# SubBus1.net
KiCad netlist of a schematic drawn in Altium Designer
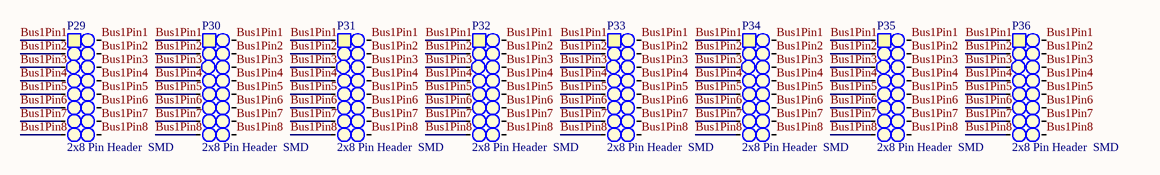
[diagram p0: SubBus1.SchDoc]

(export (version "E")
  (design (tool "Eeschema 10.0.6"))
  (components
    (comp (ref "P29")
      (value "2x8 Pin Header  SMD")
      (footprint "2X8_SMD_PH_2.54")
      (description "2.54mm, SMD")
      (libsource (lib "jclib") (part "2x8 Pin Header  SMD"))
    )
    (comp (ref "P30")
      (value "2x8 Pin Header  SMD")
      (footprint "2X8_SMD_PH_2.54")
      (description "2.54mm, SMD")
      (libsource (lib "jclib") (part "2x8 Pin Header  SMD"))
    )
    (comp (ref "P31")
      (value "2x8 Pin Header  SMD")
      (footprint "2X8_SMD_PH_2.54")
      (description "2.54mm, SMD")
      (libsource (lib "jclib") (part "2x8 Pin Header  SMD"))
    )
    (comp (ref "P32")
      (value "2x8 Pin Header  SMD")
      (footprint "2X8_SMD_PH_2.54")
      (description "2.54mm, SMD")
      (libsource (lib "jclib") (part "2x8 Pin Header  SMD"))
    )
    (comp (ref "P33")
      (value "2x8 Pin Header  SMD")
      (footprint "2X8_SMD_PH_2.54")
      (description "2.54mm, SMD")
      (libsource (lib "jclib") (part "2x8 Pin Header  SMD"))
    )
    (comp (ref "P34")
      (value "2x8 Pin Header  SMD")
      (footprint "2X8_SMD_PH_2.54")
      (description "2.54mm, SMD")
      (libsource (lib "jclib") (part "2x8 Pin Header  SMD"))
    )
    (comp (ref "P35")
      (value "2x8 Pin Header  SMD")
      (footprint "2X8_SMD_PH_2.54")
      (description "2.54mm, SMD")
      (libsource (lib "jclib") (part "2x8 Pin Header  SMD"))
    )
    (comp (ref "P36")
      (value "2x8 Pin Header  SMD")
      (footprint "2X8_SMD_PH_2.54")
      (description "2.54mm, SMD")
      (libsource (lib "jclib") (part "2x8 Pin Header  SMD"))
    )
  )
  (nets
    (net (code "1") (name "/Bus1Pin1") (class "Default")
      (node (ref "P29") (pin "1") (pinfunction "1_1") (pintype "passive"))
      (node (ref "P29") (pin "16") (pinfunction "16_16") (pintype "passive"))
      (node (ref "P30") (pin "1") (pinfunction "1_1") (pintype "passive"))
      (node (ref "P30") (pin "16") (pinfunction "16_16") (pintype "passive"))
      (node (ref "P31") (pin "1") (pinfunction "1_1") (pintype "passive"))
      (node (ref "P31") (pin "16") (pinfunction "16_16") (pintype "passive"))
      (node (ref "P32") (pin "1") (pinfunction "1_1") (pintype "passive"))
      (node (ref "P32") (pin "16") (pinfunction "16_16") (pintype "passive"))
      (node (ref "P33") (pin "1") (pinfunction "1_1") (pintype "passive"))
      (node (ref "P33") (pin "16") (pinfunction "16_16") (pintype "passive"))
      (node (ref "P34") (pin "1") (pinfunction "1_1") (pintype "passive"))
      (node (ref "P34") (pin "16") (pinfunction "16_16") (pintype "passive"))
      (node (ref "P35") (pin "1") (pinfunction "1_1") (pintype "passive"))
      (node (ref "P35") (pin "16") (pinfunction "16_16") (pintype "passive"))
      (node (ref "P36") (pin "1") (pinfunction "1_1") (pintype "passive"))
      (node (ref "P36") (pin "16") (pinfunction "16_16") (pintype "passive"))
    )
    (net (code "2") (name "/Bus1Pin2") (class "Default")
      (node (ref "P29") (pin "15") (pinfunction "15_15") (pintype "passive"))
      (node (ref "P29") (pin "2") (pinfunction "2_2") (pintype "passive"))
      (node (ref "P30") (pin "15") (pinfunction "15_15") (pintype "passive"))
      (node (ref "P30") (pin "2") (pinfunction "2_2") (pintype "passive"))
      (node (ref "P31") (pin "15") (pinfunction "15_15") (pintype "passive"))
      (node (ref "P31") (pin "2") (pinfunction "2_2") (pintype "passive"))
      (node (ref "P32") (pin "15") (pinfunction "15_15") (pintype "passive"))
      (node (ref "P32") (pin "2") (pinfunction "2_2") (pintype "passive"))
      (node (ref "P33") (pin "15") (pinfunction "15_15") (pintype "passive"))
      (node (ref "P33") (pin "2") (pinfunction "2_2") (pintype "passive"))
      (node (ref "P34") (pin "15") (pinfunction "15_15") (pintype "passive"))
      (node (ref "P34") (pin "2") (pinfunction "2_2") (pintype "passive"))
      (node (ref "P35") (pin "15") (pinfunction "15_15") (pintype "passive"))
      (node (ref "P35") (pin "2") (pinfunction "2_2") (pintype "passive"))
      (node (ref "P36") (pin "15") (pinfunction "15_15") (pintype "passive"))
      (node (ref "P36") (pin "2") (pinfunction "2_2") (pintype "passive"))
    )
    (net (code "3") (name "/Bus1Pin3") (class "Default")
      (node (ref "P29") (pin "14") (pinfunction "14_14") (pintype "passive"))
      (node (ref "P29") (pin "3") (pinfunction "3_3") (pintype "passive"))
      (node (ref "P30") (pin "14") (pinfunction "14_14") (pintype "passive"))
      (node (ref "P30") (pin "3") (pinfunction "3_3") (pintype "passive"))
      (node (ref "P31") (pin "14") (pinfunction "14_14") (pintype "passive"))
      (node (ref "P31") (pin "3") (pinfunction "3_3") (pintype "passive"))
      (node (ref "P32") (pin "14") (pinfunction "14_14") (pintype "passive"))
      (node (ref "P32") (pin "3") (pinfunction "3_3") (pintype "passive"))
      (node (ref "P33") (pin "14") (pinfunction "14_14") (pintype "passive"))
      (node (ref "P33") (pin "3") (pinfunction "3_3") (pintype "passive"))
      (node (ref "P34") (pin "14") (pinfunction "14_14") (pintype "passive"))
      (node (ref "P34") (pin "3") (pinfunction "3_3") (pintype "passive"))
      (node (ref "P35") (pin "14") (pinfunction "14_14") (pintype "passive"))
      (node (ref "P35") (pin "3") (pinfunction "3_3") (pintype "passive"))
      (node (ref "P36") (pin "14") (pinfunction "14_14") (pintype "passive"))
      (node (ref "P36") (pin "3") (pinfunction "3_3") (pintype "passive"))
    )
    (net (code "4") (name "/Bus1Pin4") (class "Default")
      (node (ref "P29") (pin "13") (pinfunction "13_13") (pintype "passive"))
      (node (ref "P29") (pin "4") (pinfunction "4_4") (pintype "passive"))
      (node (ref "P30") (pin "13") (pinfunction "13_13") (pintype "passive"))
      (node (ref "P30") (pin "4") (pinfunction "4_4") (pintype "passive"))
      (node (ref "P31") (pin "13") (pinfunction "13_13") (pintype "passive"))
      (node (ref "P31") (pin "4") (pinfunction "4_4") (pintype "passive"))
      (node (ref "P32") (pin "13") (pinfunction "13_13") (pintype "passive"))
      (node (ref "P32") (pin "4") (pinfunction "4_4") (pintype "passive"))
      (node (ref "P33") (pin "13") (pinfunction "13_13") (pintype "passive"))
      (node (ref "P33") (pin "4") (pinfunction "4_4") (pintype "passive"))
      (node (ref "P34") (pin "13") (pinfunction "13_13") (pintype "passive"))
      (node (ref "P34") (pin "4") (pinfunction "4_4") (pintype "passive"))
      (node (ref "P35") (pin "13") (pinfunction "13_13") (pintype "passive"))
      (node (ref "P35") (pin "4") (pinfunction "4_4") (pintype "passive"))
      (node (ref "P36") (pin "13") (pinfunction "13_13") (pintype "passive"))
      (node (ref "P36") (pin "4") (pinfunction "4_4") (pintype "passive"))
    )
    (net (code "5") (name "/Bus1Pin5") (class "Default")
      (node (ref "P29") (pin "12") (pinfunction "12_12") (pintype "passive"))
      (node (ref "P29") (pin "5") (pinfunction "5_5") (pintype "passive"))
      (node (ref "P30") (pin "12") (pinfunction "12_12") (pintype "passive"))
      (node (ref "P30") (pin "5") (pinfunction "5_5") (pintype "passive"))
      (node (ref "P31") (pin "12") (pinfunction "12_12") (pintype "passive"))
      (node (ref "P31") (pin "5") (pinfunction "5_5") (pintype "passive"))
      (node (ref "P32") (pin "12") (pinfunction "12_12") (pintype "passive"))
      (node (ref "P32") (pin "5") (pinfunction "5_5") (pintype "passive"))
      (node (ref "P33") (pin "12") (pinfunction "12_12") (pintype "passive"))
      (node (ref "P33") (pin "5") (pinfunction "5_5") (pintype "passive"))
      (node (ref "P34") (pin "12") (pinfunction "12_12") (pintype "passive"))
      (node (ref "P34") (pin "5") (pinfunction "5_5") (pintype "passive"))
      (node (ref "P35") (pin "12") (pinfunction "12_12") (pintype "passive"))
      (node (ref "P35") (pin "5") (pinfunction "5_5") (pintype "passive"))
      (node (ref "P36") (pin "12") (pinfunction "12_12") (pintype "passive"))
      (node (ref "P36") (pin "5") (pinfunction "5_5") (pintype "passive"))
    )
    (net (code "6") (name "/Bus1Pin6") (class "Default")
      (node (ref "P29") (pin "11") (pinfunction "11_11") (pintype "passive"))
      (node (ref "P29") (pin "6") (pinfunction "6_6") (pintype "passive"))
      (node (ref "P30") (pin "11") (pinfunction "11_11") (pintype "passive"))
      (node (ref "P30") (pin "6") (pinfunction "6_6") (pintype "passive"))
      (node (ref "P31") (pin "11") (pinfunction "11_11") (pintype "passive"))
      (node (ref "P31") (pin "6") (pinfunction "6_6") (pintype "passive"))
      (node (ref "P32") (pin "11") (pinfunction "11_11") (pintype "passive"))
      (node (ref "P32") (pin "6") (pinfunction "6_6") (pintype "passive"))
      (node (ref "P33") (pin "11") (pinfunction "11_11") (pintype "passive"))
      (node (ref "P33") (pin "6") (pinfunction "6_6") (pintype "passive"))
      (node (ref "P34") (pin "11") (pinfunction "11_11") (pintype "passive"))
      (node (ref "P34") (pin "6") (pinfunction "6_6") (pintype "passive"))
      (node (ref "P35") (pin "11") (pinfunction "11_11") (pintype "passive"))
      (node (ref "P35") (pin "6") (pinfunction "6_6") (pintype "passive"))
      (node (ref "P36") (pin "11") (pinfunction "11_11") (pintype "passive"))
      (node (ref "P36") (pin "6") (pinfunction "6_6") (pintype "passive"))
    )
    (net (code "7") (name "/Bus1Pin7") (class "Default")
      (node (ref "P29") (pin "10") (pinfunction "10_10") (pintype "passive"))
      (node (ref "P29") (pin "7") (pinfunction "7_7") (pintype "passive"))
      (node (ref "P30") (pin "10") (pinfunction "10_10") (pintype "passive"))
      (node (ref "P30") (pin "7") (pinfunction "7_7") (pintype "passive"))
      (node (ref "P31") (pin "10") (pinfunction "10_10") (pintype "passive"))
      (node (ref "P31") (pin "7") (pinfunction "7_7") (pintype "passive"))
      (node (ref "P32") (pin "10") (pinfunction "10_10") (pintype "passive"))
      (node (ref "P32") (pin "7") (pinfunction "7_7") (pintype "passive"))
      (node (ref "P33") (pin "10") (pinfunction "10_10") (pintype "passive"))
      (node (ref "P33") (pin "7") (pinfunction "7_7") (pintype "passive"))
      (node (ref "P34") (pin "10") (pinfunction "10_10") (pintype "passive"))
      (node (ref "P34") (pin "7") (pinfunction "7_7") (pintype "passive"))
      (node (ref "P35") (pin "10") (pinfunction "10_10") (pintype "passive"))
      (node (ref "P35") (pin "7") (pinfunction "7_7") (pintype "passive"))
      (node (ref "P36") (pin "10") (pinfunction "10_10") (pintype "passive"))
      (node (ref "P36") (pin "7") (pinfunction "7_7") (pintype "passive"))
    )
    (net (code "8") (name "/Bus1Pin8") (class "Default")
      (node (ref "P29") (pin "8") (pinfunction "8_8") (pintype "passive"))
      (node (ref "P29") (pin "9") (pinfunction "9_9") (pintype "passive"))
      (node (ref "P30") (pin "8") (pinfunction "8_8") (pintype "passive"))
      (node (ref "P30") (pin "9") (pinfunction "9_9") (pintype "passive"))
      (node (ref "P31") (pin "8") (pinfunction "8_8") (pintype "passive"))
      (node (ref "P31") (pin "9") (pinfunction "9_9") (pintype "passive"))
      (node (ref "P32") (pin "8") (pinfunction "8_8") (pintype "passive"))
      (node (ref "P32") (pin "9") (pinfunction "9_9") (pintype "passive"))
      (node (ref "P33") (pin "8") (pinfunction "8_8") (pintype "passive"))
      (node (ref "P33") (pin "9") (pinfunction "9_9") (pintype "passive"))
      (node (ref "P34") (pin "8") (pinfunction "8_8") (pintype "passive"))
      (node (ref "P34") (pin "9") (pinfunction "9_9") (pintype "passive"))
      (node (ref "P35") (pin "8") (pinfunction "8_8") (pintype "passive"))
      (node (ref "P35") (pin "9") (pinfunction "9_9") (pintype "passive"))
      (node (ref "P36") (pin "8") (pinfunction "8_8") (pintype "passive"))
      (node (ref "P36") (pin "9") (pinfunction "9_9") (pintype "passive"))
    )
  )
)
